# tricorder-featherwing-mk-1_4.net
KiCad netlist of a schematic drawn in EAGLE
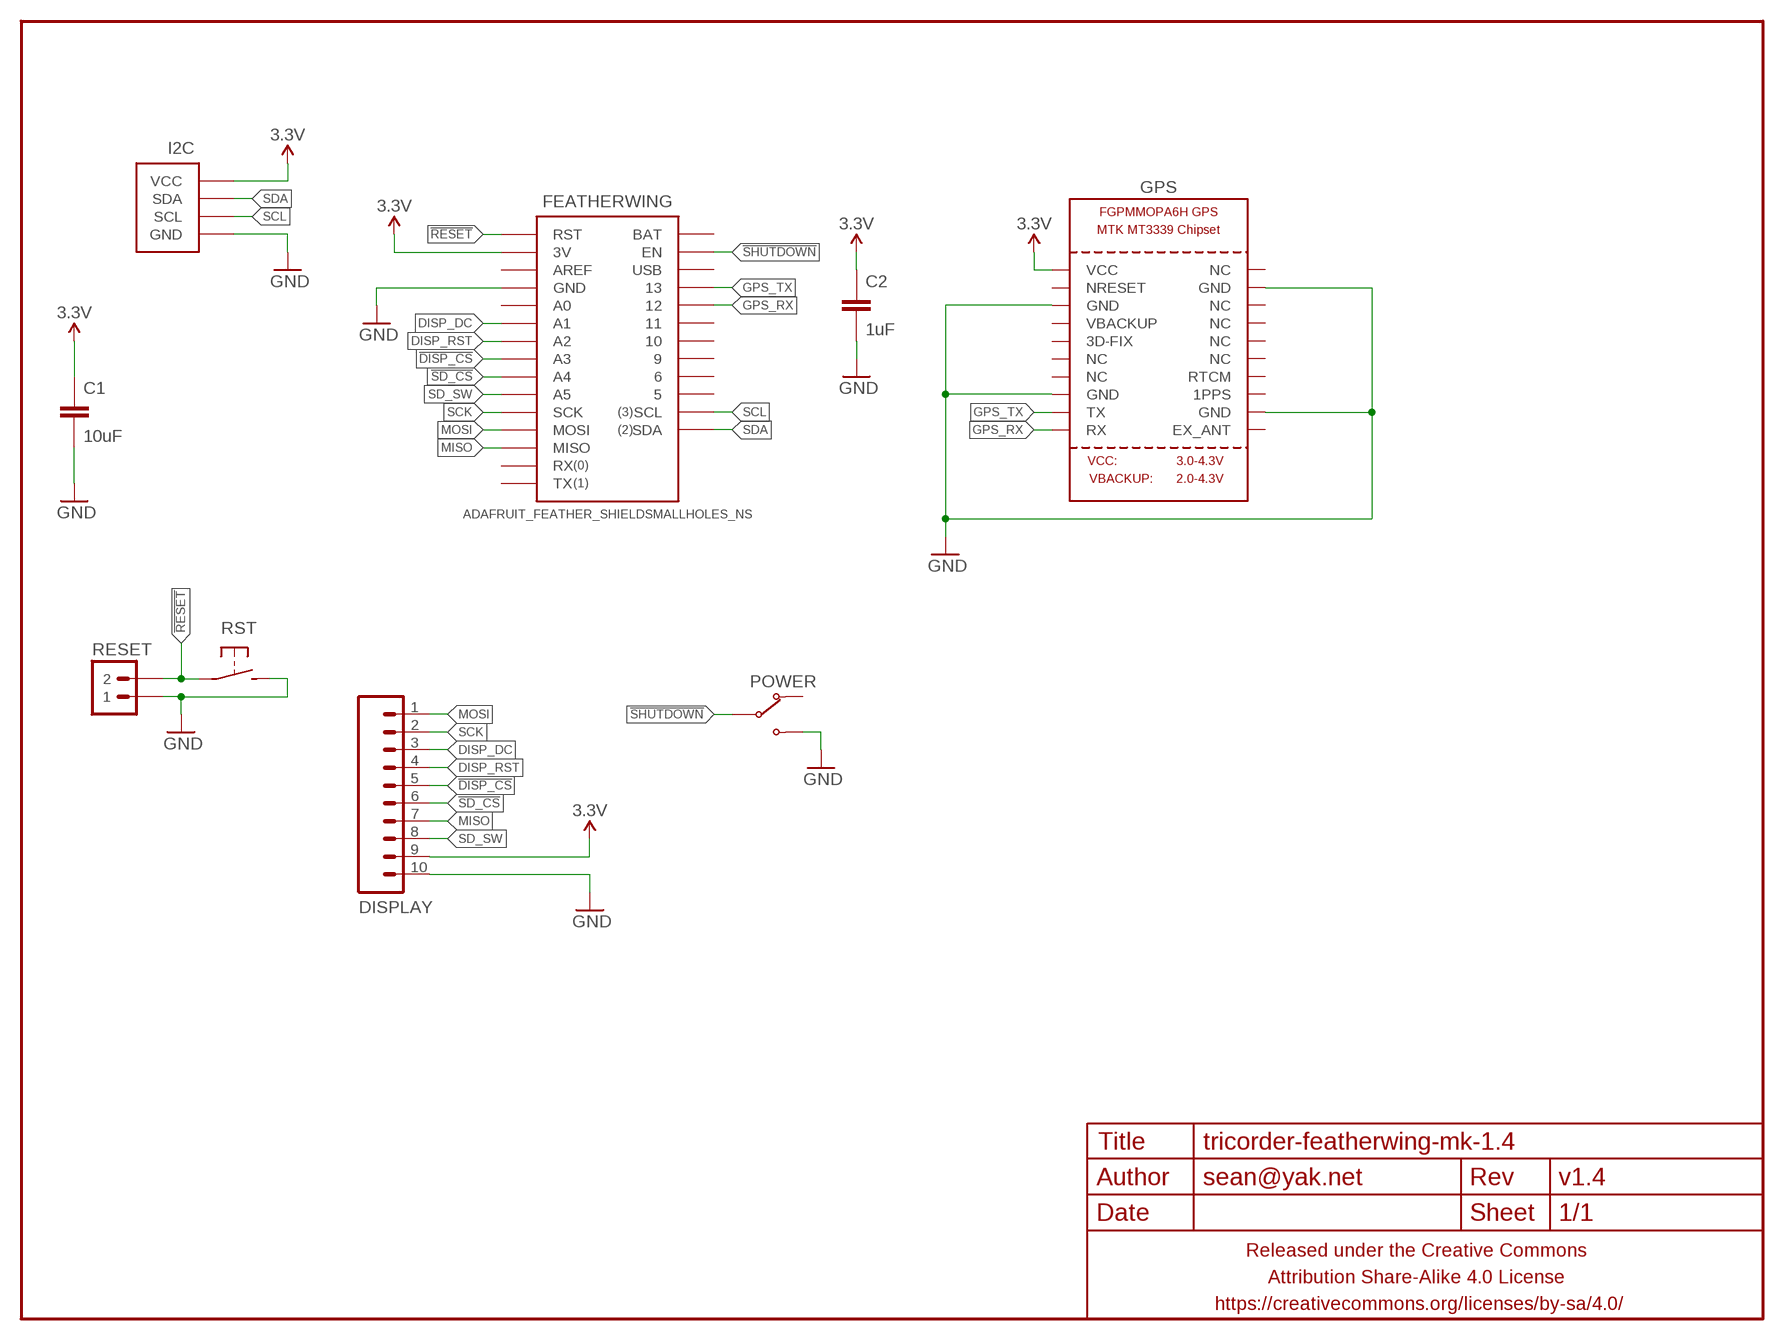
[diagram p0: schematic, sheet 1]

(export (version "E")
  (design (tool "Eeschema 10.0.6"))
  (components
    (comp (ref "C1")
      (value "10uF")
      (footprint "eagle-import:C1210")
      (libsource (lib "eagle-import") (part "CAPACITOR-CERAMICC1210"))
    )
    (comp (ref "C2")
      (value "1uF")
      (footprint "eagle-import:C0603")
      (libsource (lib "eagle-import") (part "CAPACITOR-CERAMICC0603"))
    )
    (comp (ref "DISPLAY")
      (value "M10JST-10-PH-RA-PTH")
      (footprint "eagle-import:JST-10-PH-RA-PTH")
      (libsource (lib "eagle-import") (part "M10JST-10-PH-RA-PTH"))
    )
    (comp (ref "FEATHERWING")
      (value "ADAFRUIT_FEATHER_SHIELDSMALLHOLES_NS")
      (footprint "eagle-import:ADAFRUIT_FEATHER_SMALLHOLES_NS")
      (libsource (lib "eagle-import") (part "ADAFRUIT_FEATHER_SHIELDSMALLHOLES_NS"))
    )
    (comp (ref "FRAME1")
      (value "FRAME-LETTERNO_PACKAGE")
      (footprint "eagle-import:DUMMY")
      (fields (field (name "DESIGNER") "sean@yak.net") (field (name "VERSION") "v1.4"))
      (libsource (lib "eagle-import") (part "FRAME-LETTERNO_PACKAGE"))
    )
    (comp (ref "GPS")
      (value "GPS_FGPMMOPA6H")
      (footprint "eagle-import:FGPMMOPA6H")
      (libsource (lib "eagle-import") (part "GPS_FGPMMOPA6H"))
    )
    (comp (ref "I2C")
      (value "M04-I2CJST-4-PH-RA-CENTERED")
      (footprint "eagle-import:1X04-JST-PH-RA-PTH-I2C-CENTERED")
      (libsource (lib "eagle-import") (part "M04-I2CJST-4-PH-RA-CENTERED"))
    )
    (comp (ref "POWER")
      (value "SWITCH-SPDTSMD-RA")
      (footprint "eagle-import:SWITCH-SPDT-SMD-RA")
      (libsource (lib "eagle-import") (part "SWITCH-SPDTSMD-RA"))
    )
    (comp (ref "RESET")
      (value "M02PTH-CENTERED")
      (footprint "eagle-import:1X02-CENTER")
      (libsource (lib "eagle-import") (part "M02PTH-CENTERED"))
    )
    (comp (ref "RST")
      (value "SPST-NO-TACT3MM-PTH-SMALL-PADS")
      (footprint "eagle-import:DTS-3-SMALL-PADS")
      (libsource (lib "eagle-import") (part "SPST-NO-TACT3MM-PTH-SMALL-PADS"))
    )
  )
  (nets
    (net (code "1") (name "/~{DISP_CS}") (class "Default")
      (node (ref "DISPLAY") (pin "5") (pinfunction "5_5") (pintype "passive"))
      (node (ref "FEATHERWING") (pin "A3") (pinfunction "A3_A3") (pintype "bidirectional"))
    )
    (net (code "2") (name "/~{RESET}") (class "Default")
      (node (ref "FEATHERWING") (pin "RST") (pinfunction "RST_RST") (pintype "bidirectional"))
      (node (ref "RESET") (pin "2") (pinfunction "2_2") (pintype "passive"))
      (node (ref "RST") (pin "1") (pinfunction "1_1") (pintype "passive"))
    )
    (net (code "3") (name "/~{SD_CS}") (class "Default")
      (node (ref "DISPLAY") (pin "6") (pinfunction "6_6") (pintype "passive"))
      (node (ref "FEATHERWING") (pin "A4") (pinfunction "A4_A4") (pintype "bidirectional"))
    )
    (net (code "4") (name "/~{SHUTDOWN}") (class "Default")
      (node (ref "FEATHERWING") (pin "EN") (pinfunction "EN_EN") (pintype "bidirectional"))
      (node (ref "POWER") (pin "2") (pinfunction "COM_2") (pintype "passive"))
    )
    (net (code "5") (name "3.3V") (class "Default")
      (node (ref "C1") (pin "1") (pinfunction "1_1") (pintype "passive"))
      (node (ref "C2") (pin "1") (pinfunction "1_1") (pintype "passive"))
      (node (ref "DISPLAY") (pin "9") (pinfunction "9_9") (pintype "passive"))
      (node (ref "FEATHERWING") (pin "3V") (pinfunction "3V_3V") (pintype "bidirectional"))
      (node (ref "GPS") (pin "P$1") (pinfunction "VCC_P$1") (pintype "bidirectional"))
      (node (ref "I2C") (pin "2") (pinfunction "VCC_2") (pintype "bidirectional"))
    )
    (net (code "6") (name "DISP_DC") (class "Default")
      (node (ref "DISPLAY") (pin "3") (pinfunction "3_3") (pintype "passive"))
      (node (ref "FEATHERWING") (pin "A1") (pinfunction "A1_A1") (pintype "bidirectional"))
    )
    (net (code "7") (name "DISP_RST") (class "Default")
      (node (ref "DISPLAY") (pin "4") (pinfunction "4_4") (pintype "passive"))
      (node (ref "FEATHERWING") (pin "A2") (pinfunction "A2_A2") (pintype "bidirectional"))
    )
    (net (code "8") (name "GND") (class "Default")
      (node (ref "C1") (pin "2") (pinfunction "2_2") (pintype "passive"))
      (node (ref "C2") (pin "2") (pinfunction "2_2") (pintype "passive"))
      (node (ref "DISPLAY") (pin "10") (pinfunction "10_10") (pintype "passive"))
      (node (ref "FEATHERWING") (pin "GND@0") (pinfunction "GND_GND@0") (pintype "bidirectional"))
      (node (ref "FEATHERWING") (pin "GND@1") (pinfunction "GND_GND@1") (pintype "bidirectional"))
      (node (ref "GPS") (pin "P$12") (pinfunction "GND_P$12") (pintype "bidirectional"))
      (node (ref "GPS") (pin "P$19") (pinfunction "GND_P$19") (pintype "bidirectional"))
      (node (ref "GPS") (pin "P$3") (pinfunction "GND_P$3") (pintype "bidirectional"))
      (node (ref "GPS") (pin "P$8") (pinfunction "GND_P$8") (pintype "bidirectional"))
      (node (ref "I2C") (pin "1") (pinfunction "GND_1") (pintype "bidirectional"))
      (node (ref "POWER") (pin "1") (pinfunction "NO_1") (pintype "passive"))
      (node (ref "RESET") (pin "1") (pinfunction "1_1") (pintype "passive"))
      (node (ref "RST") (pin "2") (pinfunction "2_2") (pintype "passive"))
    )
    (net (code "9") (name "GPS_RX") (class "Default")
      (node (ref "FEATHERWING") (pin "12") (pinfunction "12_12") (pintype "bidirectional"))
      (node (ref "GPS") (pin "P$10") (pinfunction "RX_P$10") (pintype "bidirectional"))
    )
    (net (code "10") (name "GPS_TX") (class "Default")
      (node (ref "FEATHERWING") (pin "13") (pinfunction "13_13") (pintype "bidirectional"))
      (node (ref "GPS") (pin "P$9") (pinfunction "TX_P$9") (pintype "bidirectional"))
    )
    (net (code "11") (name "MISO") (class "Default")
      (node (ref "DISPLAY") (pin "7") (pinfunction "7_7") (pintype "passive"))
      (node (ref "FEATHERWING") (pin "MISO") (pinfunction "MISO_MISO") (pintype "bidirectional"))
    )
    (net (code "12") (name "MOSI") (class "Default")
      (node (ref "DISPLAY") (pin "1") (pinfunction "1_1") (pintype "passive"))
      (node (ref "FEATHERWING") (pin "MOSI") (pinfunction "MOSI_MOSI") (pintype "bidirectional"))
    )
    (net (code "13") (name "SCK") (class "Default")
      (node (ref "DISPLAY") (pin "2") (pinfunction "2_2") (pintype "passive"))
      (node (ref "FEATHERWING") (pin "SCK") (pinfunction "SCK_SCK") (pintype "bidirectional"))
    )
    (net (code "14") (name "SCL") (class "Default")
      (node (ref "FEATHERWING") (pin "SCL") (pinfunction "SCL_SCL") (pintype "bidirectional"))
      (node (ref "I2C") (pin "4") (pinfunction "SCL_4") (pintype "bidirectional"))
    )
    (net (code "15") (name "SDA") (class "Default")
      (node (ref "FEATHERWING") (pin "SDA") (pinfunction "SDA_SDA") (pintype "bidirectional"))
      (node (ref "I2C") (pin "3") (pinfunction "SDA_3") (pintype "bidirectional"))
    )
    (net (code "16") (name "SD_SW") (class "Default")
      (node (ref "DISPLAY") (pin "8") (pinfunction "8_8") (pintype "passive"))
      (node (ref "FEATHERWING") (pin "A5") (pinfunction "A5_A5") (pintype "bidirectional"))
    )
    (net (code "17") (name "unconnected-(FEATHERWING-Pad5)") (class "Default")
      (node (ref "FEATHERWING") (pin "5") (pinfunction "5_5") (pintype "bidirectional"))
    )
    (net (code "18") (name "unconnected-(FEATHERWING-Pad6)") (class "Default")
      (node (ref "FEATHERWING") (pin "6") (pinfunction "6_6") (pintype "bidirectional"))
    )
    (net (code "19") (name "unconnected-(FEATHERWING-Pad9)") (class "Default")
      (node (ref "FEATHERWING") (pin "9") (pinfunction "9_9") (pintype "bidirectional"))
    )
    (net (code "20") (name "unconnected-(FEATHERWING-Pad10)") (class "Default")
      (node (ref "FEATHERWING") (pin "10") (pinfunction "10_10") (pintype "bidirectional"))
    )
    (net (code "21") (name "unconnected-(FEATHERWING-Pad11)") (class "Default")
      (node (ref "FEATHERWING") (pin "11") (pinfunction "11_11") (pintype "bidirectional"))
    )
    (net (code "22") (name "unconnected-(FEATHERWING-PadA0)") (class "Default")
      (node (ref "FEATHERWING") (pin "A0") (pinfunction "A0_A0") (pintype "bidirectional"))
    )
    (net (code "23") (name "unconnected-(FEATHERWING-PadAREF)") (class "Default")
      (node (ref "FEATHERWING") (pin "AREF") (pinfunction "AREF_AREF") (pintype "bidirectional"))
    )
    (net (code "24") (name "unconnected-(FEATHERWING-PadBAT)") (class "Default")
      (node (ref "FEATHERWING") (pin "BAT") (pinfunction "BAT_BAT") (pintype "bidirectional"))
    )
    (net (code "25") (name "unconnected-(FEATHERWING-PadRX)") (class "Default")
      (node (ref "FEATHERWING") (pin "RX") (pinfunction "RX_RX") (pintype "bidirectional"))
    )
    (net (code "26") (name "unconnected-(FEATHERWING-PadTX)") (class "Default")
      (node (ref "FEATHERWING") (pin "TX") (pinfunction "TX_TX") (pintype "bidirectional"))
    )
    (net (code "27") (name "unconnected-(FEATHERWING-PadUSB)") (class "Default")
      (node (ref "FEATHERWING") (pin "USB") (pinfunction "USB_USB") (pintype "bidirectional"))
    )
    (net (code "28") (name "unconnected-(GPS-1PPS-PadP$13)") (class "Default")
      (node (ref "GPS") (pin "P$13") (pinfunction "1PPS_P$13") (pintype "bidirectional"))
    )
    (net (code "29") (name "unconnected-(GPS-3D-FIX-PadP$5)") (class "Default")
      (node (ref "GPS") (pin "P$5") (pinfunction "3D-FIX_P$5") (pintype "bidirectional"))
    )
    (net (code "30") (name "unconnected-(GPS-EX_ANT-PadP$11)") (class "Default")
      (node (ref "GPS") (pin "P$11") (pinfunction "EX_ANT_P$11") (pintype "bidirectional"))
    )
    (net (code "31") (name "unconnected-(GPS-NC-PadP$6)") (class "Default")
      (node (ref "GPS") (pin "P$6") (pinfunction "NC_P$6") (pintype "bidirectional"))
    )
    (net (code "32") (name "unconnected-(GPS-NC-PadP$7)") (class "Default")
      (node (ref "GPS") (pin "P$7") (pinfunction "NC_P$7") (pintype "bidirectional"))
    )
    (net (code "33") (name "unconnected-(GPS-NC-PadP$15)") (class "Default")
      (node (ref "GPS") (pin "P$15") (pinfunction "NC_P$15") (pintype "bidirectional"))
    )
    (net (code "34") (name "unconnected-(GPS-NC-PadP$16)") (class "Default")
      (node (ref "GPS") (pin "P$16") (pinfunction "NC_P$16") (pintype "bidirectional"))
    )
    (net (code "35") (name "unconnected-(GPS-NC-PadP$17)") (class "Default")
      (node (ref "GPS") (pin "P$17") (pinfunction "NC_P$17") (pintype "bidirectional"))
    )
    (net (code "36") (name "unconnected-(GPS-NC-PadP$18)") (class "Default")
      (node (ref "GPS") (pin "P$18") (pinfunction "NC_P$18") (pintype "bidirectional"))
    )
    (net (code "37") (name "unconnected-(GPS-NC-PadP$20)") (class "Default")
      (node (ref "GPS") (pin "P$20") (pinfunction "NC_P$20") (pintype "bidirectional"))
    )
    (net (code "38") (name "unconnected-(GPS-NRESET-PadP$2)") (class "Default")
      (node (ref "GPS") (pin "P$2") (pinfunction "NRESET_P$2") (pintype "bidirectional"))
    )
    (net (code "39") (name "unconnected-(GPS-RTCM-PadP$14)") (class "Default")
      (node (ref "GPS") (pin "P$14") (pinfunction "RTCM_P$14") (pintype "bidirectional"))
    )
    (net (code "40") (name "unconnected-(GPS-VBACKUP-PadP$4)") (class "Default")
      (node (ref "GPS") (pin "P$4") (pinfunction "VBACKUP_P$4") (pintype "bidirectional"))
    )
    (net (code "41") (name "unconnected-(POWER-NC-Pad3)") (class "Default")
      (node (ref "POWER") (pin "3") (pinfunction "NC_3") (pintype "passive"))
    )
  )
)
